# lcstudio-sdcard-leveler.net
KiCad netlist of a schematic drawn in EAGLE
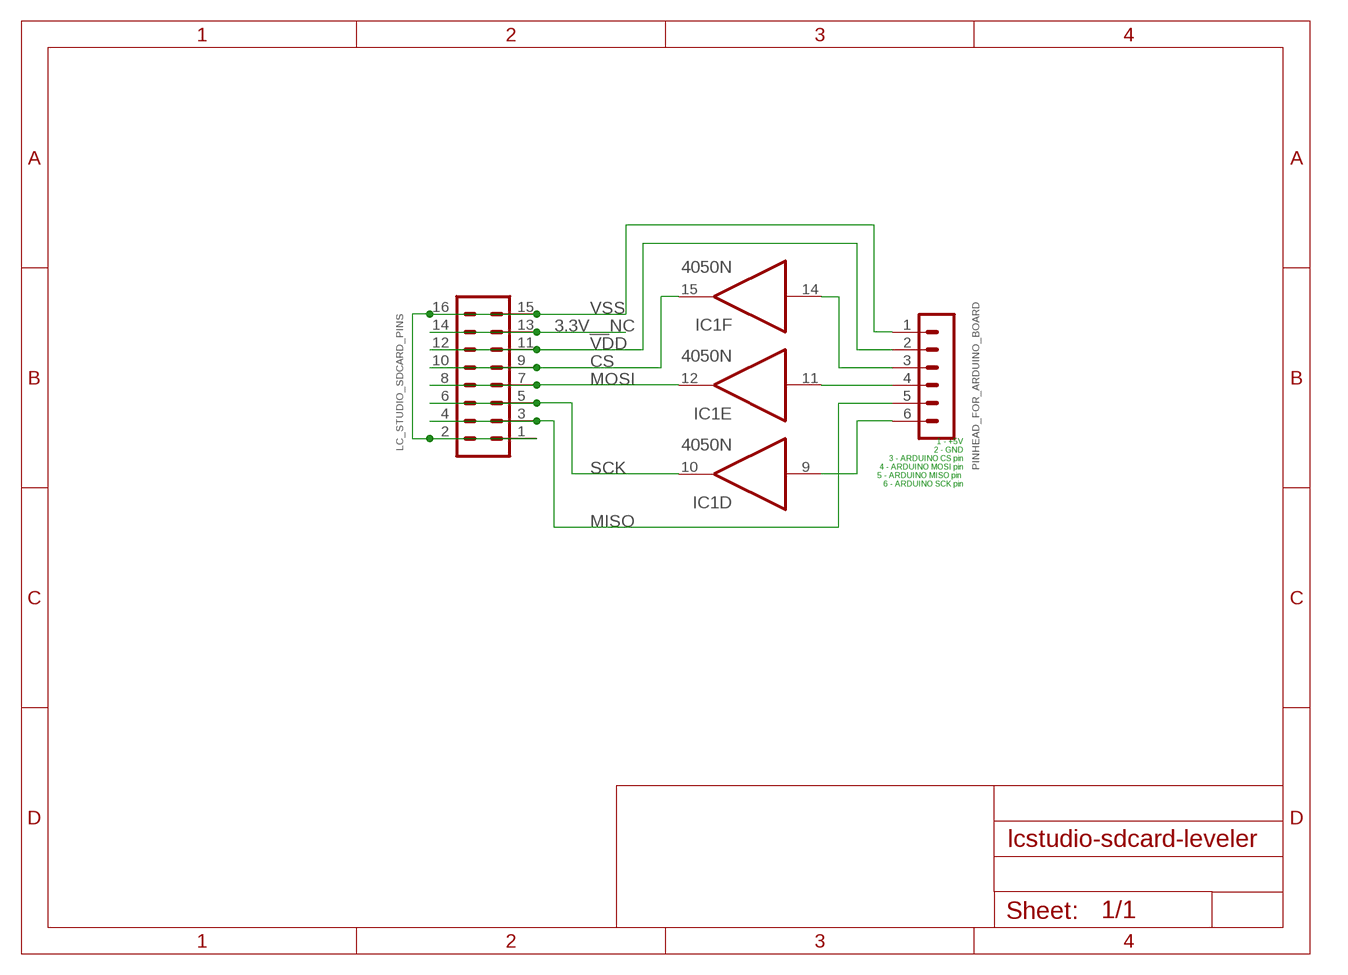
[diagram p0: schematic, sheet 1]

(export (version "E")
  (design (tool "Eeschema 10.0.6"))
  (components
    (comp (ref "IC1")
      (value "4050N")
      (footprint "eagle-import:DIL16")
      (libsource (lib "eagle-import") (part "4050N"))
    )
    (comp (ref "LC_STUDIO_SDCARD_PINS")
      (value "MA08-2")
      (footprint "eagle-import:MA08-2")
      (libsource (lib "eagle-import") (part "MA08-2"))
    )
    (comp (ref "PINHEAD_FOR_ARDUINO_BOARD")
      (value "MA06-1")
      (footprint "eagle-import:MA06-1")
      (libsource (lib "eagle-import") (part "MA06-1"))
    )
  )
  (nets
    (net (code "1") (name "/3.3V__NC") (class "Default")
      (node (ref "LC_STUDIO_SDCARD_PINS") (pin "13") (pinfunction "13_13") (pintype "passive"))
      (node (ref "LC_STUDIO_SDCARD_PINS") (pin "14") (pinfunction "14_14") (pintype "passive"))
    )
    (net (code "2") (name "/CS") (class "Default")
      (node (ref "IC1") (pin "15") (pinfunction "O_15") (pintype "output"))
      (node (ref "LC_STUDIO_SDCARD_PINS") (pin "10") (pinfunction "10_10") (pintype "passive"))
      (node (ref "LC_STUDIO_SDCARD_PINS") (pin "9") (pinfunction "9_9") (pintype "passive"))
    )
    (net (code "3") (name "/MISO") (class "Default")
      (node (ref "LC_STUDIO_SDCARD_PINS") (pin "3") (pinfunction "3_3") (pintype "passive"))
      (node (ref "LC_STUDIO_SDCARD_PINS") (pin "4") (pinfunction "4_4") (pintype "passive"))
      (node (ref "PINHEAD_FOR_ARDUINO_BOARD") (pin "5") (pinfunction "5_5") (pintype "passive"))
    )
    (net (code "4") (name "/MOSI") (class "Default")
      (node (ref "IC1") (pin "12") (pinfunction "O_12") (pintype "output"))
      (node (ref "LC_STUDIO_SDCARD_PINS") (pin "7") (pinfunction "7_7") (pintype "passive"))
      (node (ref "LC_STUDIO_SDCARD_PINS") (pin "8") (pinfunction "8_8") (pintype "passive"))
    )
    (net (code "5") (name "/SCK") (class "Default")
      (node (ref "IC1") (pin "10") (pinfunction "O_10") (pintype "output"))
      (node (ref "LC_STUDIO_SDCARD_PINS") (pin "5") (pinfunction "5_5") (pintype "passive"))
      (node (ref "LC_STUDIO_SDCARD_PINS") (pin "6") (pinfunction "6_6") (pintype "passive"))
    )
    (net (code "6") (name "/VDD") (class "Default")
      (node (ref "LC_STUDIO_SDCARD_PINS") (pin "11") (pinfunction "11_11") (pintype "passive"))
      (node (ref "LC_STUDIO_SDCARD_PINS") (pin "12") (pinfunction "12_12") (pintype "passive"))
      (node (ref "PINHEAD_FOR_ARDUINO_BOARD") (pin "2") (pinfunction "2_2") (pintype "passive"))
    )
    (net (code "7") (name "/VSS") (class "Default")
      (node (ref "LC_STUDIO_SDCARD_PINS") (pin "1") (pinfunction "1_1") (pintype "passive"))
      (node (ref "LC_STUDIO_SDCARD_PINS") (pin "15") (pinfunction "15_15") (pintype "passive"))
      (node (ref "LC_STUDIO_SDCARD_PINS") (pin "16") (pinfunction "16_16") (pintype "passive"))
      (node (ref "LC_STUDIO_SDCARD_PINS") (pin "2") (pinfunction "2_2") (pintype "passive"))
      (node (ref "PINHEAD_FOR_ARDUINO_BOARD") (pin "1") (pinfunction "1_1") (pintype "passive"))
    )
    (net (code "8") (name "Net-(IC1D-I)") (class "Default")
      (node (ref "IC1") (pin "9") (pinfunction "I_9") (pintype "input"))
      (node (ref "PINHEAD_FOR_ARDUINO_BOARD") (pin "6") (pinfunction "6_6") (pintype "passive"))
    )
    (net (code "9") (name "Net-(IC1E-I)") (class "Default")
      (node (ref "IC1") (pin "11") (pinfunction "I_11") (pintype "input"))
      (node (ref "PINHEAD_FOR_ARDUINO_BOARD") (pin "4") (pinfunction "4_4") (pintype "passive"))
    )
    (net (code "10") (name "Net-(IC1F-I)") (class "Default")
      (node (ref "IC1") (pin "14") (pinfunction "I_14") (pintype "input"))
      (node (ref "PINHEAD_FOR_ARDUINO_BOARD") (pin "3") (pinfunction "3_3") (pintype "passive"))
    )
  )
)
